# 02-ESP32.net
KiCad netlist of a schematic drawn in Altium Designer
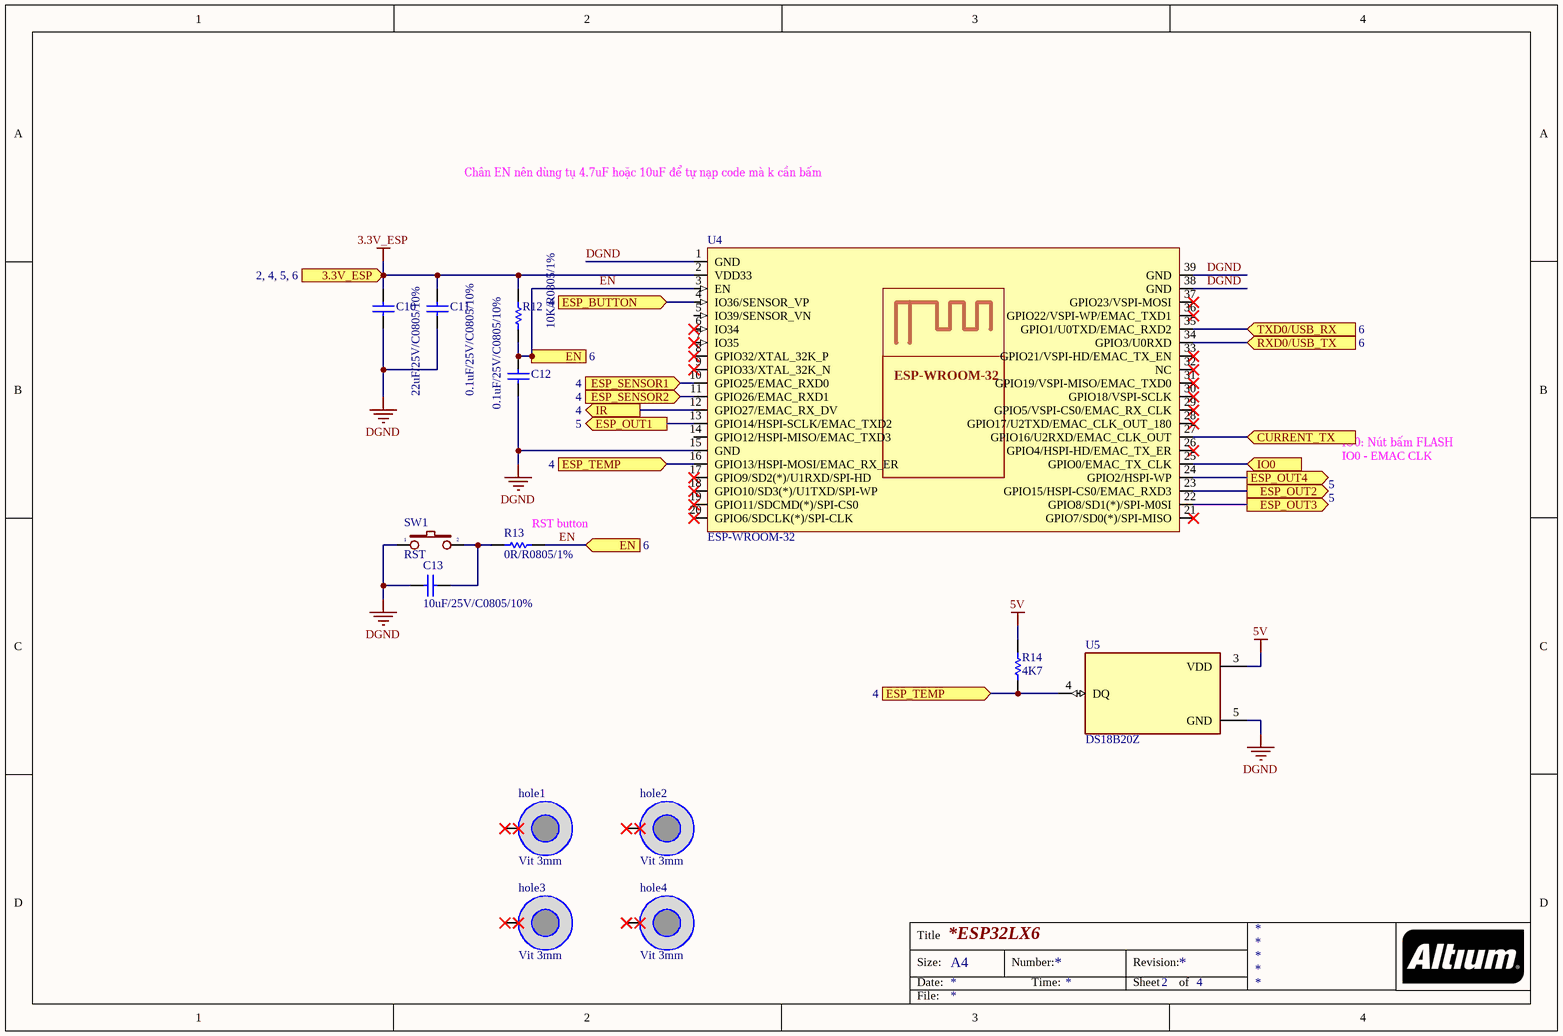
[diagram p0: 02-ESP32.SchDoc]

(export (version "E")
  (design (tool "Eeschema 10.0.6"))
  (components
    (comp (ref "C10")
      (value "22uF/25V/C0805/10%")
      (footprint "CAP_CERA_C2012(CC0805INCH)")
      (description "22µF ±20% 25V Ceramic Capacitor X5R 0805 (2012 Metric)")
      (fields (field (name "MANUFACTURER") "Tariff Applied"))
      (libsource (lib "GSHT_181013") (part "0.1uF/50V/C0603/10%"))
    )
    (comp (ref "C11")
      (value "0.1uF/25V/C0805/10%")
      (footprint "CAP_CERA_C2012(CC0805INCH)")
      (description "0.1µF ±10% 25V Ceramic Capacitor X7R 0805 (2012 Metric)")
      (libsource (lib "GSHT_181013") (part "0.1uF/50V/C0603/10%"))
    )
    (comp (ref "C12")
      (value "0.1uF/25V/C0805/10%")
      (footprint "CAP_CERA_C2012(CC0805INCH)")
      (description "0.1µF ±10% 25V Ceramic Capacitor X7R 0805 (2012 Metric)")
      (libsource (lib "GSHT_181013") (part "0.1uF/50V/C0603/10%"))
    )
    (comp (ref "C13")
      (value "10uF/25V/C0805/10%")
      (footprint "CAP_CERA_C2012(CC0805INCH)")
      (description "0.1µF ±10% 25V Ceramic Capacitor X7R 0805 (2012 Metric)")
      (libsource (lib "GSHT_181013") (part "0.1uF/50V/C0603/10%"))
    )
    (comp (ref "hole1") (value "Vit 3mm") (footprint "Screw 3.0") (libsource (lib "lpson") (part "Vit 3mm")))
    (comp (ref "hole2") (value "Vit 3mm") (footprint "Screw 3.0") (libsource (lib "lpson") (part "Vit 3mm")))
    (comp (ref "hole3") (value "Vit 3mm") (footprint "Screw 3.0") (libsource (lib "lpson") (part "Vit 3mm")))
    (comp (ref "hole4") (value "Vit 3mm") (footprint "Screw 3.0") (libsource (lib "lpson") (part "Vit 3mm")))
    (comp (ref "R12")
      (value "10K/R0805/1%")
      (footprint "Res 0805 SMD")
      (description "10 kOhms ±1% 0.125W, 1/8W Chip Resistor 0805 (2012 Metric) Thick Film")
      (libsource (lib "GSHT_181013") (part "200K/R0603/1%"))
    )
    (comp (ref "R13")
      (value "0R/R0805/1%")
      (footprint "Res 0805 SMD")
      (description "0 Ohms Jumper 0.125W, 1/8W Chip Resistor 0805 (2012 Metric) Automotive AEC-Q200 Thick Film")
      (libsource (lib "GSHT_181013") (part "200K/R0603/1%"))
    )
    (comp (ref "R14")
      (value "4K7")
      (footprint "Res 0805 SMD")
      (description "4k7 Ohms Jumper 0.125W, 1/8W Chip Resistor 0805 (2012 Metric)")
      (libsource (lib "GSHT_181013") (part "200K/R0603/1%"))
    )
    (comp (ref "SW1")
      (value "RST")
      (footprint "Button 3x4mm")
      (description "SWITCH TACTILE SPST-NO 0.05A 12V")
      (libsource (lib "lpson") (part "SW2"))
    )
    (comp (ref "U4")
      (value "ESP-WROOM-32")
      (footprint "ESP32 WROOM")
      (description "ESP-WROOM-32 (8MB), WIFI MODULE 64 MBITS SPI FLASH")
      (libsource (lib "lpson") (part "ESP-WROOM-32"))
    )
    (comp (ref "U5")
      (value "DS18B20Z")
      (footprint "PCB-ALLinONE:SOIC127P600X175-8N")
      (description "Temperature Sensor Digital, Local -55Â°C ~ 125Â°C 12 b 8-SOIC")
      (fields (field (name "MP") "DS18B20Z+") (field (name "MF") "Maxim Integrated"))
      (libsource (lib "Schlib1") (part "DS18B20Z"))
    )
  )
  (nets
    (net (code "1") (name "/CURRENT_TX") (class "Default")
      (node (ref "U4") (pin "27") (pinfunction "GPIO16/U2RXD/EMAC_CLK_OUT_27") (pintype "passive"))
    )
    (net (code "2") (name "/EN") (class "Default")
      (node (ref "C12") (pin "2") (pinfunction "2_2") (pintype "passive"))
      (node (ref "R12") (pin "2") (pinfunction "2_2") (pintype "passive"))
      (node (ref "R13") (pin "2") (pinfunction "2_2") (pintype "passive"))
      (node (ref "U4") (pin "3") (pinfunction "EN_3") (pintype "input"))
    )
    (net (code "3") (name "/ESP_BUTTON") (class "Default")
      (node (ref "U4") (pin "4") (pinfunction "IO36/SENSOR_VP_4") (pintype "input"))
    )
    (net (code "4") (name "/ESP_OUT1") (class "Default")
      (node (ref "U4") (pin "13") (pinfunction "GPIO14/HSPI-SCLK/EMAC_TXD2_13") (pintype "passive"))
    )
    (net (code "5") (name "/ESP_OUT2") (class "Default")
      (node (ref "U4") (pin "23") (pinfunction "GPIO15/HSPI-CS0/EMAC_RXD3_23") (pintype "passive"))
    )
    (net (code "6") (name "/ESP_OUT3") (class "Default")
      (node (ref "U4") (pin "22") (pinfunction "GPIO8/SD1(*)/SPI-M0SI_22") (pintype "passive"))
    )
    (net (code "7") (name "/ESP_OUT4") (class "Default")
      (node (ref "U4") (pin "24") (pinfunction "GPIO2/HSPI-WP_24") (pintype "passive"))
    )
    (net (code "8") (name "/ESP_SENSOR1") (class "Default")
      (node (ref "U4") (pin "10") (pinfunction "GPIO25/EMAC_RXD0_10") (pintype "passive"))
    )
    (net (code "9") (name "/ESP_SENSOR2") (class "Default")
      (node (ref "U4") (pin "11") (pinfunction "GPIO26/EMAC_RXD1_11") (pintype "passive"))
    )
    (net (code "10") (name "/ESP_TEMP") (class "Default")
      (node (ref "R14") (pin "1") (pinfunction "1_1") (pintype "passive"))
      (node (ref "U4") (pin "16") (pinfunction "GPIO13/HSPI-MOSI/EMAC_RX_ER_16") (pintype "passive"))
      (node (ref "U5") (pin "4") (pinfunction "DQ_4") (pintype "bidirectional"))
    )
    (net (code "11") (name "/IO0") (class "Default")
      (node (ref "U4") (pin "25") (pinfunction "GPIO0/EMAC_TX_CLK_25") (pintype "passive"))
    )
    (net (code "12") (name "/IR") (class "Default")
      (node (ref "U4") (pin "12") (pinfunction "GPIO27/EMAC_RX_DV_12") (pintype "passive"))
    )
    (net (code "13") (name "/RXD0{slash}USB_TX") (class "Default")
      (node (ref "U4") (pin "34") (pinfunction "GPIO3/U0RXD_34") (pintype "passive"))
    )
    (net (code "14") (name "/TXD0{slash}USB_RX") (class "Default")
      (node (ref "U4") (pin "35") (pinfunction "GPIO1/U0TXD/EMAC_RXD2_35") (pintype "passive"))
    )
    (net (code "15") (name "3.3V_ESP") (class "Default")
      (node (ref "C10") (pin "2") (pinfunction "2_2") (pintype "passive"))
      (node (ref "C11") (pin "2") (pinfunction "2_2") (pintype "passive"))
      (node (ref "R12") (pin "1") (pinfunction "1_1") (pintype "passive"))
      (node (ref "U4") (pin "2") (pinfunction "VDD33_2") (pintype "passive"))
    )
    (net (code "16") (name "5V") (class "Default")
      (node (ref "R14") (pin "2") (pinfunction "2_2") (pintype "passive"))
      (node (ref "U5") (pin "3") (pinfunction "VDD_3") (pintype "power_in"))
    )
    (net (code "17") (name "DGND") (class "Default")
      (node (ref "C10") (pin "1") (pinfunction "1_1") (pintype "passive"))
      (node (ref "C11") (pin "1") (pinfunction "1_1") (pintype "passive"))
      (node (ref "C12") (pin "1") (pinfunction "1_1") (pintype "passive"))
      (node (ref "C13") (pin "2") (pinfunction "2_2") (pintype "passive"))
      (node (ref "SW1") (pin "1") (pinfunction "1_1") (pintype "passive"))
      (node (ref "U4") (pin "1") (pinfunction "GND_1") (pintype "passive"))
      (node (ref "U4") (pin "15") (pinfunction "GND_15") (pintype "passive"))
      (node (ref "U4") (pin "38") (pinfunction "GND_38") (pintype "passive"))
      (node (ref "U4") (pin "39") (pinfunction "GND_39") (pintype "passive"))
      (node (ref "U5") (pin "5") (pinfunction "GND_5") (pintype "power_in"))
    )
    (net (code "18") (name "Net-(C13-Pad1)") (class "Default")
      (node (ref "C13") (pin "1") (pinfunction "1_1") (pintype "passive"))
      (node (ref "R13") (pin "1") (pinfunction "1_1") (pintype "passive"))
      (node (ref "SW1") (pin "2") (pinfunction "2_2") (pintype "passive"))
    )
    (net (code "19") (name "unconnected-(U4-GPIO4{slash}HSPI-HD{slash}EMAC_TX_ER-Pad26)") (class "Default")
      (node (ref "U4") (pin "26") (pinfunction "GPIO4/HSPI-HD/EMAC_TX_ER_26") (pintype "passive+no_connect"))
    )
    (net (code "20") (name "unconnected-(U4-GPIO5{slash}VSPI-CS0{slash}EMAC_RX_CLK-Pad29)") (class "Default")
      (node (ref "U4") (pin "29") (pinfunction "GPIO5/VSPI-CS0/EMAC_RX_CLK_29") (pintype "passive+no_connect"))
    )
    (net (code "21") (name "unconnected-(U4-GPIO6{slash}SDCLK(*){slash}SPI-CLK-Pad20)") (class "Default")
      (node (ref "U4") (pin "20") (pinfunction "GPIO6/SDCLK(*)/SPI-CLK_20") (pintype "passive+no_connect"))
    )
    (net (code "22") (name "unconnected-(U4-GPIO7{slash}SD0(*){slash}SPI-MISO-Pad21)") (class "Default")
      (node (ref "U4") (pin "21") (pinfunction "GPIO7/SD0(*)/SPI-MISO_21") (pintype "passive+no_connect"))
    )
    (net (code "23") (name "unconnected-(U4-GPIO9{slash}SD2(*){slash}U1RXD{slash}SPI-HD-Pad17)") (class "Default")
      (node (ref "U4") (pin "17") (pinfunction "GPIO9/SD2(*)/U1RXD/SPI-HD_17") (pintype "passive+no_connect"))
    )
    (net (code "24") (name "unconnected-(U4-GPIO10{slash}SD3(*){slash}U1TXD{slash}SPI-WP-Pad18)") (class "Default")
      (node (ref "U4") (pin "18") (pinfunction "GPIO10/SD3(*)/U1TXD/SPI-WP_18") (pintype "passive+no_connect"))
    )
    (net (code "25") (name "unconnected-(U4-GPIO11{slash}SDCMD(*){slash}SPI-CS0-Pad19)") (class "Default")
      (node (ref "U4") (pin "19") (pinfunction "GPIO11/SDCMD(*)/SPI-CS0_19") (pintype "passive+no_connect"))
    )
    (net (code "26") (name "unconnected-(U4-GPIO12{slash}HSPI-MISO{slash}EMAC_TXD3-Pad14)") (class "Default")
      (node (ref "U4") (pin "14") (pinfunction "GPIO12/HSPI-MISO/EMAC_TXD3_14") (pintype "passive"))
    )
    (net (code "27") (name "unconnected-(U4-GPIO17{slash}U2TXD{slash}EMAC_CLK_OUT_180-Pad28)") (class "Default")
      (node (ref "U4") (pin "28") (pinfunction "GPIO17/U2TXD/EMAC_CLK_OUT_180_28") (pintype "passive+no_connect"))
    )
    (net (code "28") (name "unconnected-(U4-GPIO18{slash}VSPI-SCLK-Pad30)") (class "Default")
      (node (ref "U4") (pin "30") (pinfunction "GPIO18/VSPI-SCLK_30") (pintype "passive+no_connect"))
    )
    (net (code "29") (name "unconnected-(U4-GPIO19{slash}VSPI-MISO{slash}EMAC_TXD0-Pad31)") (class "Default")
      (node (ref "U4") (pin "31") (pinfunction "GPIO19/VSPI-MISO/EMAC_TXD0_31") (pintype "passive+no_connect"))
    )
    (net (code "30") (name "unconnected-(U4-GPIO21{slash}VSPI-HD{slash}EMAC_TX_EN-Pad33)") (class "Default")
      (node (ref "U4") (pin "33") (pinfunction "GPIO21/VSPI-HD/EMAC_TX_EN_33") (pintype "passive+no_connect"))
    )
    (net (code "31") (name "unconnected-(U4-GPIO22{slash}VSPI-WP{slash}EMAC_TXD1-Pad36)") (class "Default")
      (node (ref "U4") (pin "36") (pinfunction "GPIO22/VSPI-WP/EMAC_TXD1_36") (pintype "passive+no_connect"))
    )
    (net (code "32") (name "unconnected-(U4-GPIO23{slash}VSPI-MOSI-Pad37)") (class "Default")
      (node (ref "U4") (pin "37") (pinfunction "GPIO23/VSPI-MOSI_37") (pintype "passive+no_connect"))
    )
    (net (code "33") (name "unconnected-(U4-GPIO32{slash}XTAL_32K_P-Pad8)") (class "Default")
      (node (ref "U4") (pin "8") (pinfunction "GPIO32/XTAL_32K_P_8") (pintype "passive+no_connect"))
    )
    (net (code "34") (name "unconnected-(U4-GPIO33{slash}XTAL_32K_N-Pad9)") (class "Default")
      (node (ref "U4") (pin "9") (pinfunction "GPIO33/XTAL_32K_N_9") (pintype "passive+no_connect"))
    )
    (net (code "35") (name "unconnected-(U4-IO34-Pad6)") (class "Default")
      (node (ref "U4") (pin "6") (pinfunction "IO34_6") (pintype "input+no_connect"))
    )
    (net (code "36") (name "unconnected-(U4-IO35-Pad7)") (class "Default")
      (node (ref "U4") (pin "7") (pinfunction "IO35_7") (pintype "input+no_connect"))
    )
    (net (code "37") (name "unconnected-(U4-IO39{slash}SENSOR_VN-Pad5)") (class "Default")
      (node (ref "U4") (pin "5") (pinfunction "IO39/SENSOR_VN_5") (pintype "input"))
    )
    (net (code "38") (name "unconnected-(U4-NC-Pad32)") (class "Default")
      (node (ref "U4") (pin "32") (pinfunction "NC_32") (pintype "passive+no_connect"))
    )
    (net (code "39") (name "unconnected-(hole1-hole-Pad1)") (class "Default")
      (node (ref "hole1") (pin "1") (pinfunction "hole_1") (pintype "passive+no_connect"))
    )
    (net (code "40") (name "unconnected-(hole2-hole-Pad1)") (class "Default")
      (node (ref "hole2") (pin "1") (pinfunction "hole_1") (pintype "passive+no_connect"))
    )
    (net (code "41") (name "unconnected-(hole3-hole-Pad1)") (class "Default")
      (node (ref "hole3") (pin "1") (pinfunction "hole_1") (pintype "passive+no_connect"))
    )
    (net (code "42") (name "unconnected-(hole4-hole-Pad1)") (class "Default")
      (node (ref "hole4") (pin "1") (pinfunction "hole_1") (pintype "passive+no_connect"))
    )
  )
)
